# DM1098FFC_RPi3b__Connector.net
KiCad netlist of a schematic drawn in Altium Designer
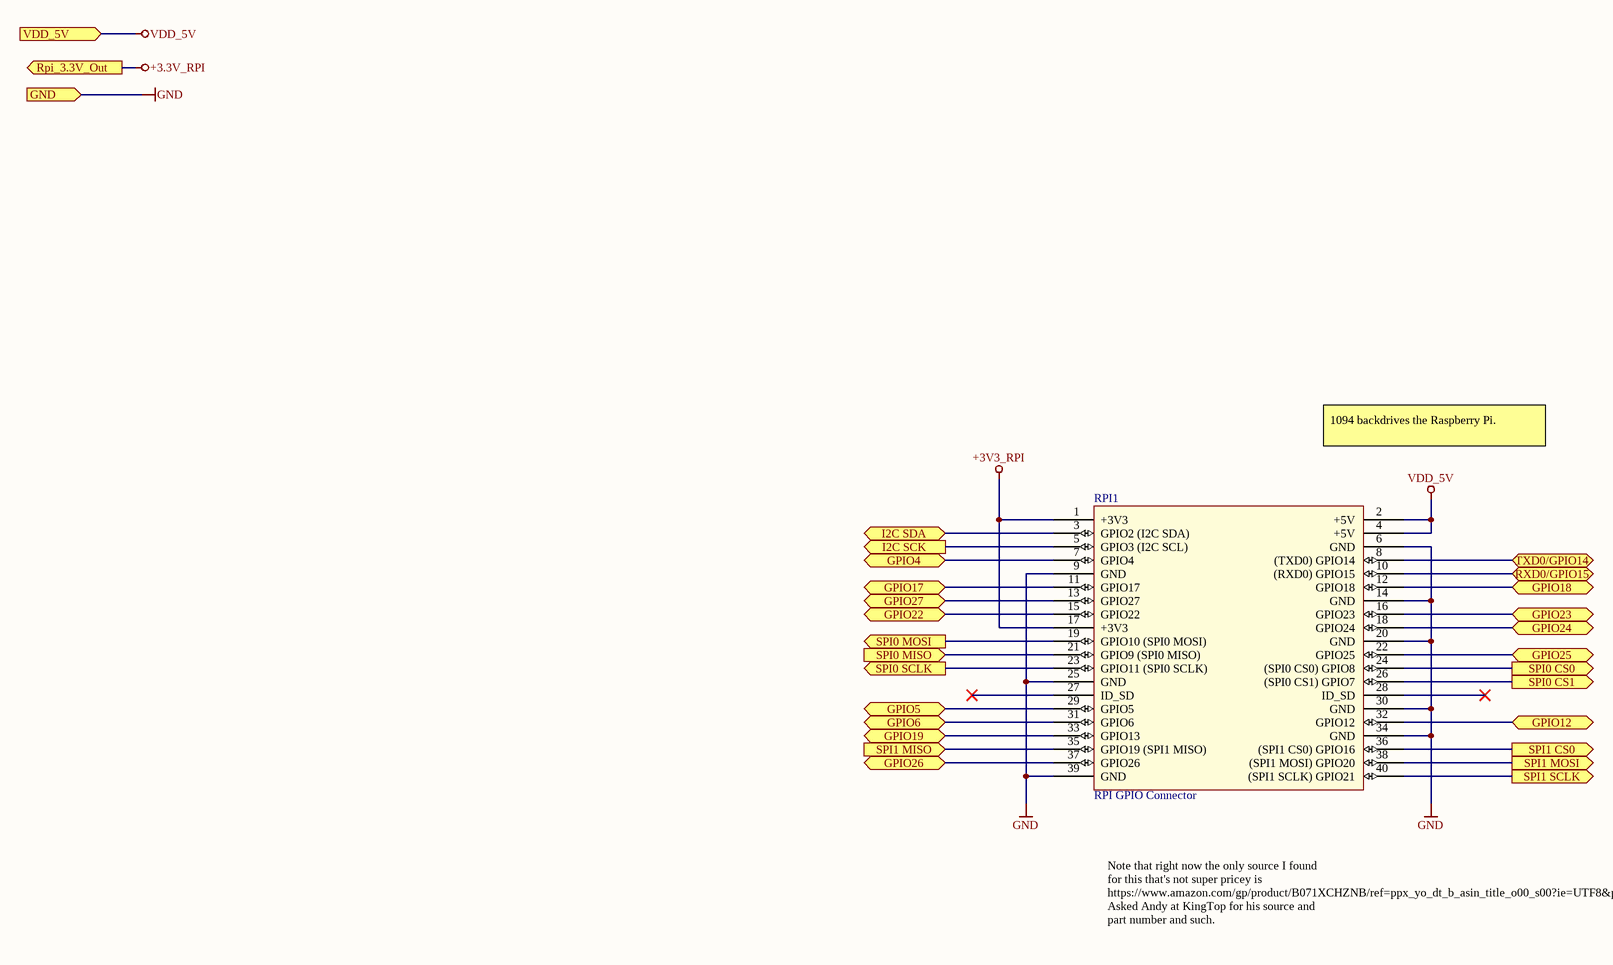
[diagram p0: DM1098FFC_RPi3b+_Connector.SchDoc]

(export (version "E")
  (design (tool "Eeschema 10.0.6"))
  (components
    (comp (ref "RPI1")
      (value "RPI GPIO Connector")
      (footprint "Luxonis:rpi-hat-40-socket")
      (description "GPIO Header for Raspberry Pi A+/B+/Pi 2/Pi 3 - 2x20")
      (libsource (lib "Luxonis") (part "RPi HAT 40 Pin Connector"))
    )
  )
  (nets
    (net (code "2") (name "+3V3_RPI") (class "Default")
      (node (ref "RPI1") (pin "1") (pinfunction "+3V3_1") (pintype "power_in"))
      (node (ref "RPI1") (pin "17") (pinfunction "+3V3_17") (pintype "power_in"))
    )
    (net (code "3") (name "/GPIO4") (class "Default")
      (node (ref "RPI1") (pin "7") (pinfunction "GPIO4_7") (pintype "bidirectional"))
    )
    (net (code "4") (name "/GPIO5") (class "Default")
      (node (ref "RPI1") (pin "29") (pinfunction "GPIO5_29") (pintype "bidirectional"))
    )
    (net (code "5") (name "/GPIO6") (class "Default")
      (node (ref "RPI1") (pin "31") (pinfunction "GPIO6_31") (pintype "bidirectional"))
    )
    (net (code "6") (name "/GPIO12") (class "Default")
      (node (ref "RPI1") (pin "32") (pinfunction "GPIO12_32") (pintype "bidirectional"))
    )
    (net (code "7") (name "/GPIO17") (class "Default")
      (node (ref "RPI1") (pin "11") (pinfunction "GPIO17_11") (pintype "bidirectional"))
    )
    (net (code "8") (name "/GPIO18") (class "Default")
      (node (ref "RPI1") (pin "12") (pinfunction "GPIO18_12") (pintype "bidirectional"))
    )
    (net (code "9") (name "/GPIO19") (class "Default")
      (node (ref "RPI1") (pin "33") (pinfunction "GPIO13_33") (pintype "bidirectional"))
    )
    (net (code "10") (name "/GPIO22") (class "Default")
      (node (ref "RPI1") (pin "15") (pinfunction "GPIO22_15") (pintype "bidirectional"))
    )
    (net (code "11") (name "/GPIO23") (class "Default")
      (node (ref "RPI1") (pin "16") (pinfunction "GPIO23_16") (pintype "bidirectional"))
    )
    (net (code "12") (name "/GPIO24") (class "Default")
      (node (ref "RPI1") (pin "18") (pinfunction "GPIO24_18") (pintype "bidirectional"))
    )
    (net (code "13") (name "/GPIO25") (class "Default")
      (node (ref "RPI1") (pin "22") (pinfunction "GPIO25_22") (pintype "bidirectional"))
    )
    (net (code "14") (name "/GPIO26") (class "Default")
      (node (ref "RPI1") (pin "37") (pinfunction "GPIO26_37") (pintype "bidirectional"))
    )
    (net (code "15") (name "/GPIO27") (class "Default")
      (node (ref "RPI1") (pin "13") (pinfunction "GPIO27_13") (pintype "bidirectional"))
    )
    (net (code "16") (name "/I2C SCK") (class "Default")
      (node (ref "RPI1") (pin "5") (pinfunction "GPIO3_(I2C_SCL)_5") (pintype "bidirectional"))
    )
    (net (code "17") (name "/I2C SDA") (class "Default")
      (node (ref "RPI1") (pin "3") (pinfunction "GPIO2_(I2C_SDA)_3") (pintype "bidirectional"))
    )
    (net (code "18") (name "/RXD0{slash}GPIO15") (class "Default")
      (node (ref "RPI1") (pin "10") (pinfunction "(RXD0)_GPIO15_10") (pintype "bidirectional"))
    )
    (net (code "19") (name "/SPI0 CS0") (class "Default")
      (node (ref "RPI1") (pin "24") (pinfunction "(SPI0_CS0)_GPIO8_24") (pintype "bidirectional"))
    )
    (net (code "20") (name "/SPI0 CS1") (class "Default")
      (node (ref "RPI1") (pin "26") (pinfunction "(SPI0_CS1)_GPIO7_26") (pintype "bidirectional"))
    )
    (net (code "21") (name "/SPI0 MISO") (class "Default")
      (node (ref "RPI1") (pin "21") (pinfunction "GPIO9_(SPI0_MISO)_21") (pintype "bidirectional"))
    )
    (net (code "22") (name "/SPI0 MOSI") (class "Default")
      (node (ref "RPI1") (pin "19") (pinfunction "GPIO10_(SPI0_MOSI)_19") (pintype "bidirectional"))
    )
    (net (code "23") (name "/SPI0 SCLK") (class "Default")
      (node (ref "RPI1") (pin "23") (pinfunction "GPIO11_(SPI0_SCLK)_23") (pintype "bidirectional"))
    )
    (net (code "24") (name "/SPI1 CS0") (class "Default")
      (node (ref "RPI1") (pin "36") (pinfunction "(SPI1_CS0)_GPIO16_36") (pintype "bidirectional"))
    )
    (net (code "25") (name "/SPI1 MISO") (class "Default")
      (node (ref "RPI1") (pin "35") (pinfunction "GPIO19_(SPI1_MISO)_35") (pintype "bidirectional"))
    )
    (net (code "26") (name "/SPI1 MOSI") (class "Default")
      (node (ref "RPI1") (pin "38") (pinfunction "(SPI1_MOSI)_GPIO20_38") (pintype "bidirectional"))
    )
    (net (code "27") (name "/SPI1 SCLK") (class "Default")
      (node (ref "RPI1") (pin "40") (pinfunction "(SPI1_SCLK)_GPIO21_40") (pintype "bidirectional"))
    )
    (net (code "28") (name "/TXD0{slash}GPIO14") (class "Default")
      (node (ref "RPI1") (pin "8") (pinfunction "(TXD0)_GPIO14_8") (pintype "bidirectional"))
    )
    (net (code "29") (name "GND") (class "Default")
      (node (ref "RPI1") (pin "14") (pinfunction "GND_14") (pintype "passive"))
      (node (ref "RPI1") (pin "20") (pinfunction "GND_20") (pintype "passive"))
      (node (ref "RPI1") (pin "25") (pinfunction "GND_25") (pintype "passive"))
      (node (ref "RPI1") (pin "30") (pinfunction "GND_30") (pintype "passive"))
      (node (ref "RPI1") (pin "34") (pinfunction "GND_34") (pintype "passive"))
      (node (ref "RPI1") (pin "39") (pinfunction "GND_39") (pintype "passive"))
      (node (ref "RPI1") (pin "6") (pinfunction "GND_6") (pintype "passive"))
      (node (ref "RPI1") (pin "9") (pinfunction "GND_9") (pintype "passive"))
    )
    (net (code "30") (name "VDD_5V") (class "Default")
      (node (ref "RPI1") (pin "2") (pinfunction "+5V_2") (pintype "power_in"))
      (node (ref "RPI1") (pin "4") (pinfunction "+5V_4") (pintype "power_in"))
    )
    (net (code "31") (name "unconnected-(RPI1-ID_SD-Pad27)") (class "Default")
      (node (ref "RPI1") (pin "27") (pinfunction "ID_SD_27") (pintype "passive+no_connect"))
    )
    (net (code "32") (name "unconnected-(RPI1-ID_SD-Pad28)") (class "Default")
      (node (ref "RPI1") (pin "28") (pinfunction "ID_SD_28") (pintype "passive+no_connect"))
    )
  )
)
